# starduino.net
KiCad netlist of a schematic drawn in EAGLE
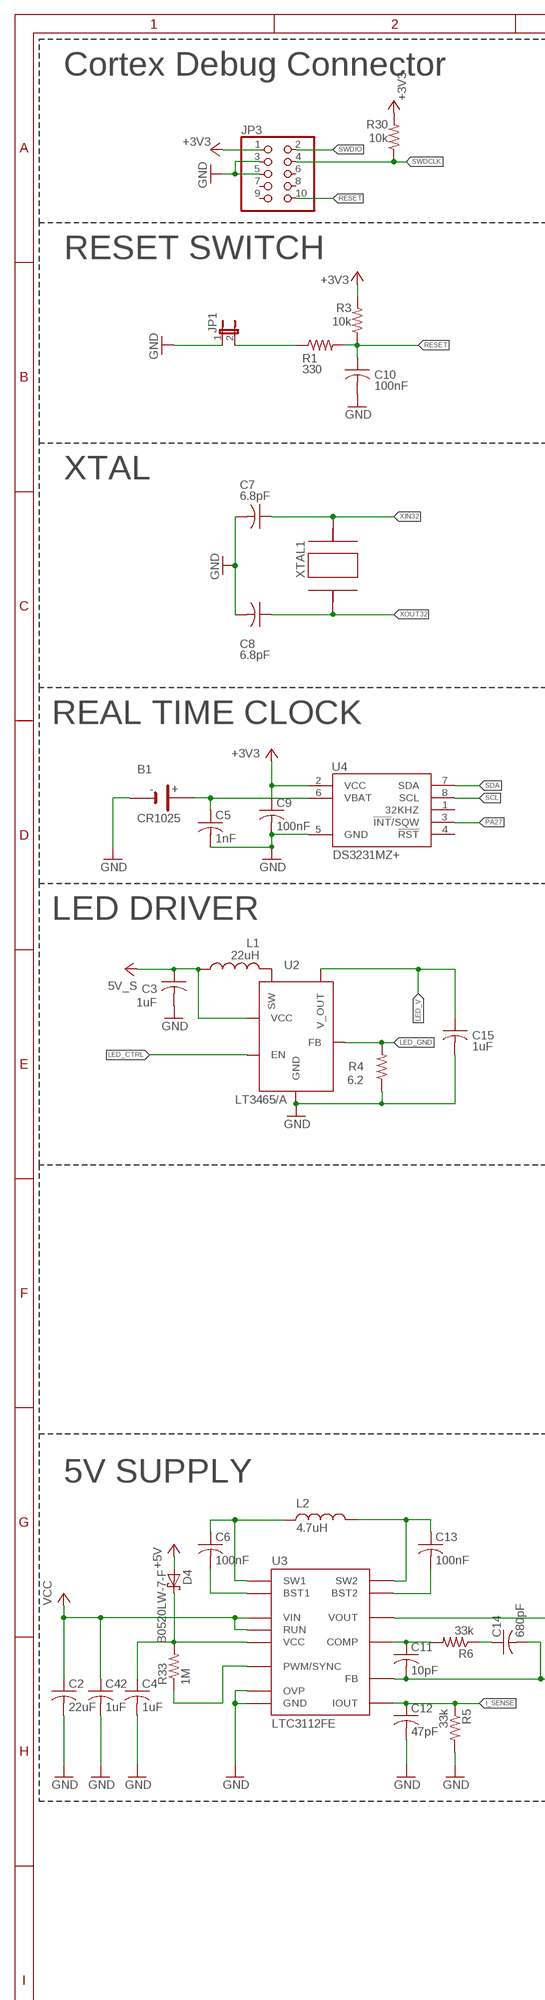
[diagram p0: schematic, sheet 1, part 1 of 2]
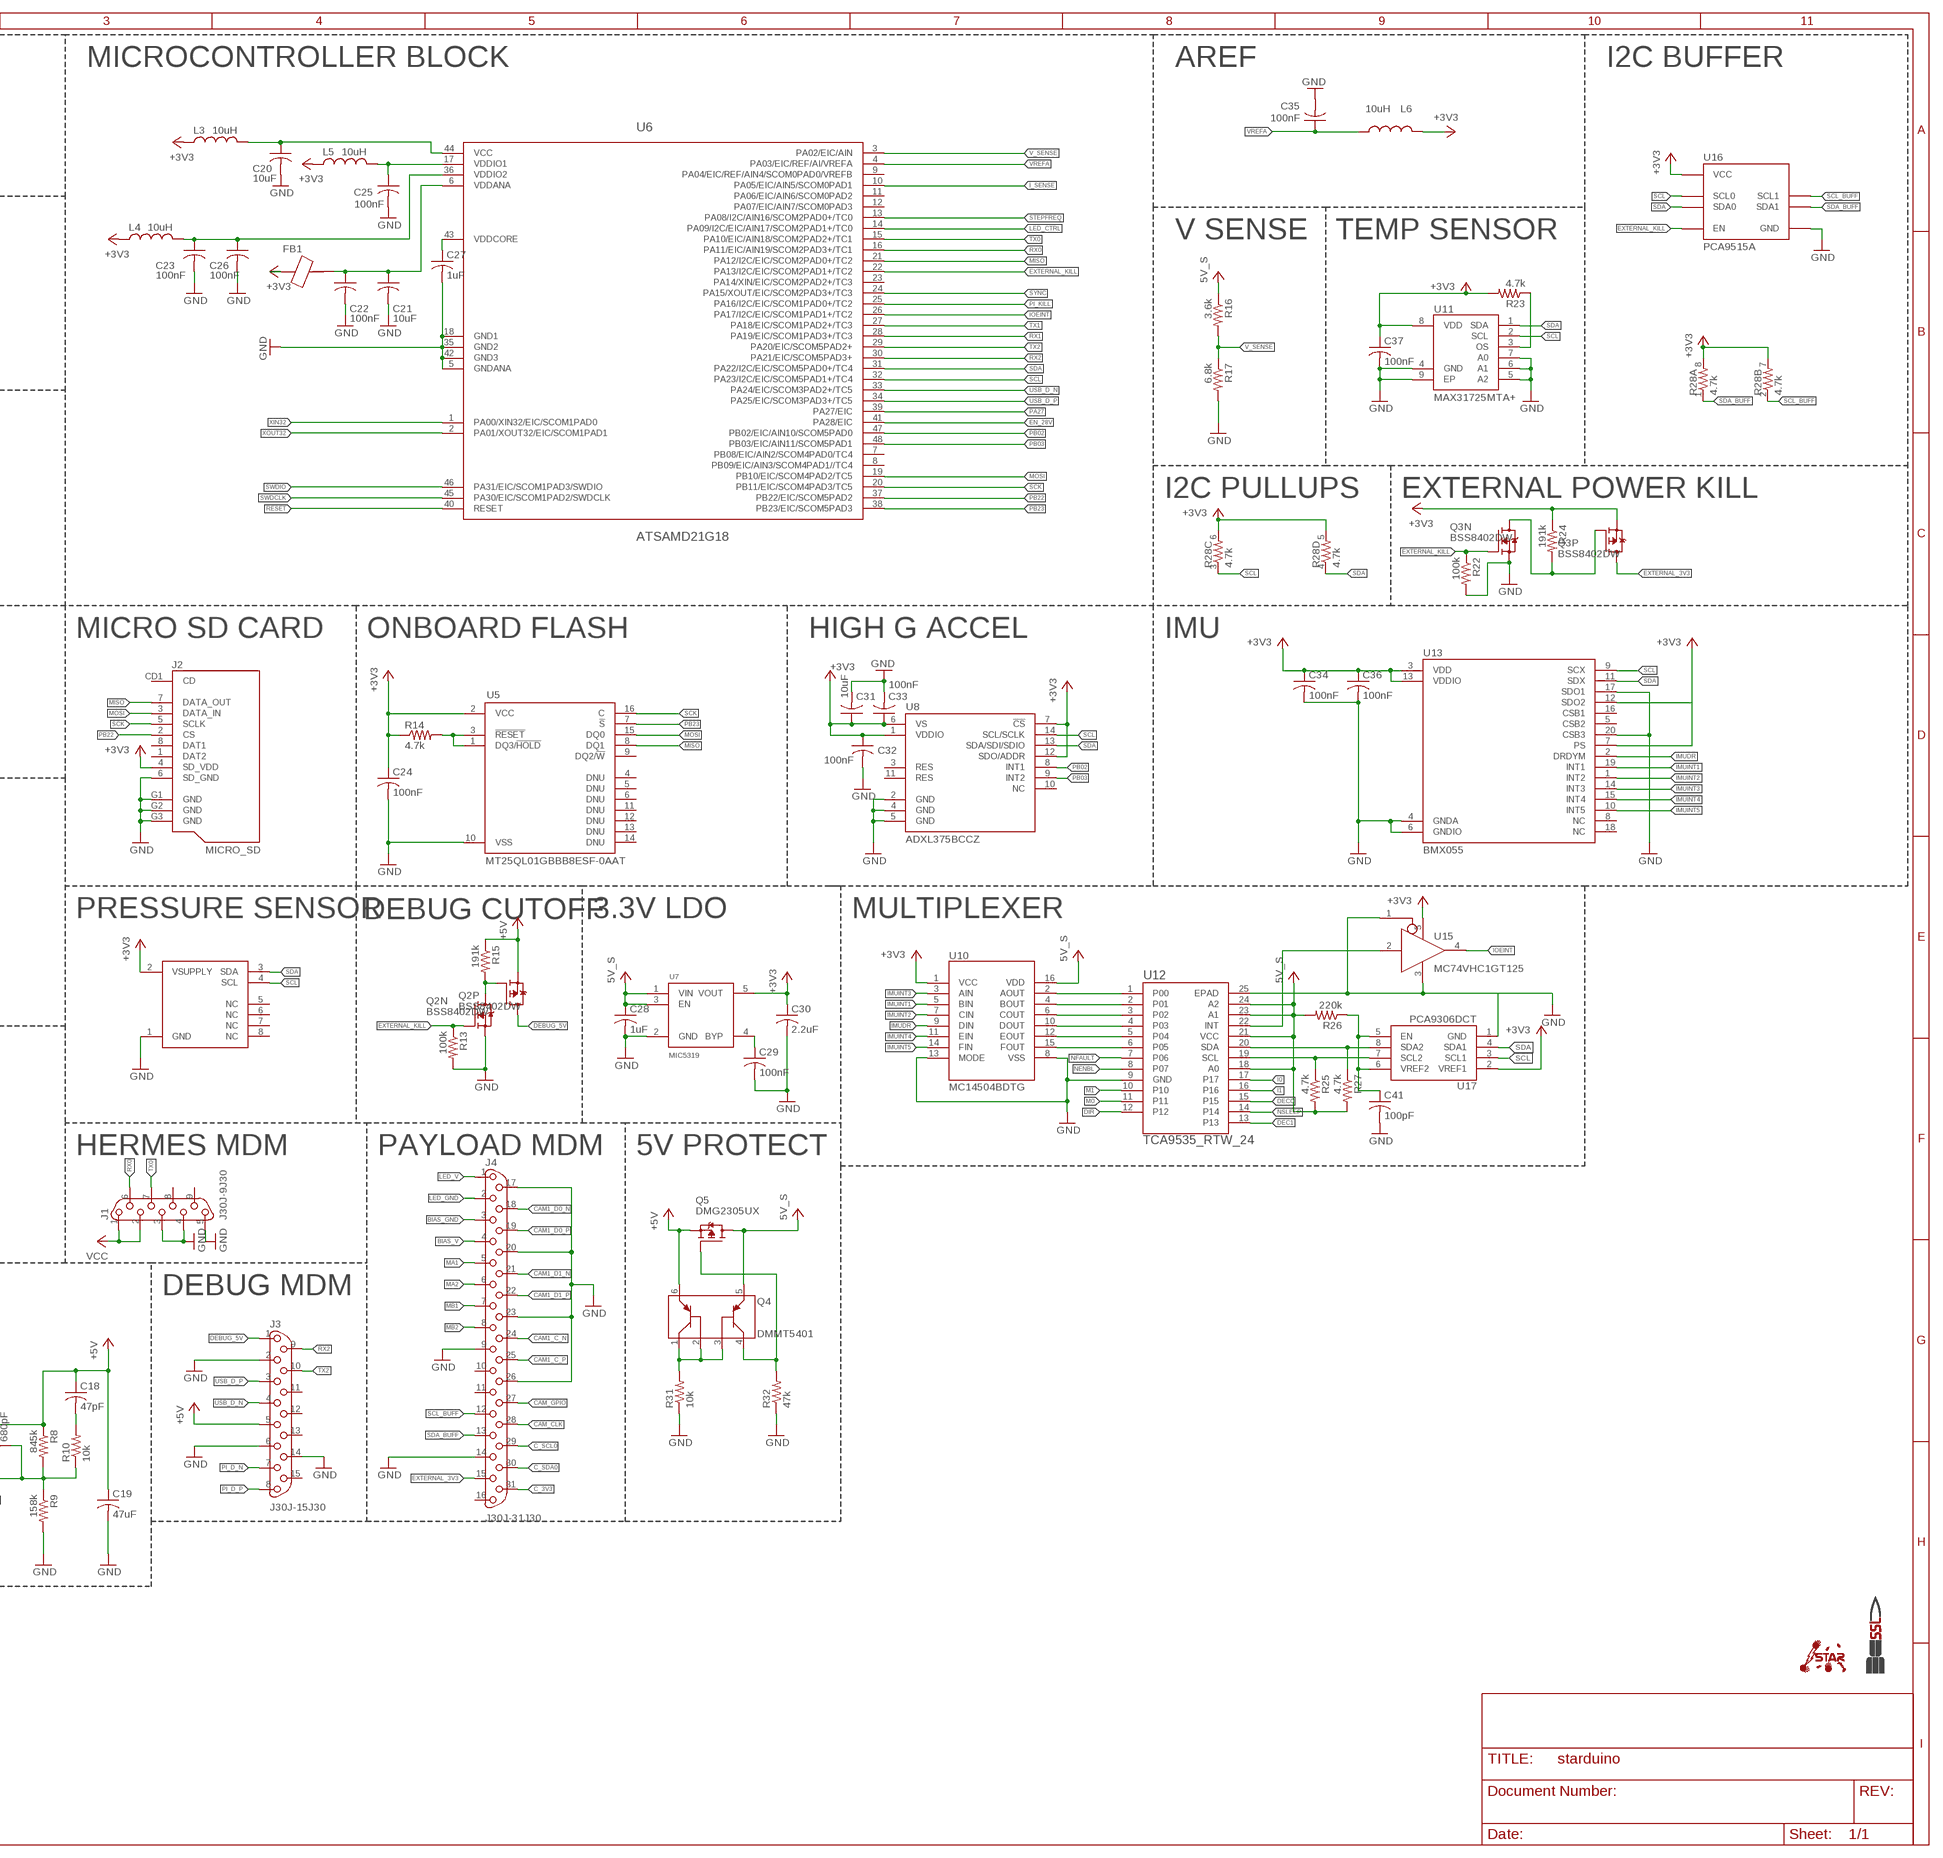
[diagram p1: schematic, sheet 1, part 2 of 2]

(export (version "E")
  (design (tool "Eeschema 10.0.6"))
  (components
    (comp (ref "B1")
      (value "CR1025")
      (footprint "eagle-import:CR1025")
      (libsource (lib "eagle-import") (part "CR1025"))
    )
    (comp (ref "C2")
      (value "22uF")
      (footprint "eagle-import:C1206")
      (libsource (lib "eagle-import") (part "resistor_C-USC1206"))
    )
    (comp (ref "C3")
      (value "1uF")
      (footprint "eagle-import:C0603")
      (libsource (lib "eagle-import") (part "resistor_C-USC0603"))
    )
    (comp (ref "C4")
      (value "1uF")
      (footprint "eagle-import:C0603")
      (libsource (lib "eagle-import") (part "resistor_C-USC0603"))
    )
    (comp (ref "C5")
      (value "1nF")
      (footprint "eagle-import:C0603")
      (libsource (lib "eagle-import") (part "resistor_C-USC0603"))
    )
    (comp (ref "C6")
      (value "100nF")
      (footprint "eagle-import:C0603")
      (libsource (lib "eagle-import") (part "resistor_C-USC0603"))
    )
    (comp (ref "C7")
      (value "6.8pF")
      (footprint "eagle-import:C0603")
      (libsource (lib "eagle-import") (part "resistor_C-USC0603"))
    )
    (comp (ref "C8")
      (value "6.8pF")
      (footprint "eagle-import:C0603")
      (libsource (lib "eagle-import") (part "resistor_C-USC0603"))
    )
    (comp (ref "C9")
      (value "100nF")
      (footprint "eagle-import:C0603")
      (libsource (lib "eagle-import") (part "resistor_C-USC0603"))
    )
    (comp (ref "C10")
      (value "100nF")
      (footprint "eagle-import:C0603")
      (libsource (lib "eagle-import") (part "resistor_C-USC0603"))
    )
    (comp (ref "C11")
      (value "10pF")
      (footprint "eagle-import:C0603")
      (libsource (lib "eagle-import") (part "resistor_C-USC0603"))
    )
    (comp (ref "C12")
      (value "47pF")
      (footprint "eagle-import:C0603")
      (libsource (lib "eagle-import") (part "resistor_C-USC0603"))
    )
    (comp (ref "C13")
      (value "100nF")
      (footprint "eagle-import:C0603")
      (libsource (lib "eagle-import") (part "resistor_C-USC0603"))
    )
    (comp (ref "C14")
      (value "680pF")
      (footprint "eagle-import:C0603")
      (libsource (lib "eagle-import") (part "resistor_C-USC0603"))
    )
    (comp (ref "C15")
      (value "1uF")
      (footprint "eagle-import:C0603")
      (libsource (lib "eagle-import") (part "resistor_C-USC0603"))
    )
    (comp (ref "C18")
      (value "47pF")
      (footprint "eagle-import:C0603")
      (libsource (lib "eagle-import") (part "resistor_C-USC0603"))
    )
    (comp (ref "C19")
      (value "47uF")
      (footprint "eagle-import:C1210")
      (libsource (lib "eagle-import") (part "resistor_C-USC1210"))
    )
    (comp (ref "C20")
      (value "10uF")
      (footprint "eagle-import:C0603")
      (libsource (lib "eagle-import") (part "resistor_C-USC0603"))
    )
    (comp (ref "C21")
      (value "10uF")
      (footprint "eagle-import:C0603")
      (libsource (lib "eagle-import") (part "resistor_C-USC0603"))
    )
    (comp (ref "C22")
      (value "100nF")
      (footprint "eagle-import:C0603")
      (libsource (lib "eagle-import") (part "resistor_C-USC0603"))
    )
    (comp (ref "C23")
      (value "100nF")
      (footprint "eagle-import:C0603")
      (libsource (lib "eagle-import") (part "resistor_C-USC0603"))
    )
    (comp (ref "C24")
      (value "100nF")
      (footprint "eagle-import:C0603")
      (libsource (lib "eagle-import") (part "resistor_C-USC0603"))
    )
    (comp (ref "C25")
      (value "100nF")
      (footprint "eagle-import:C0603")
      (libsource (lib "eagle-import") (part "resistor_C-USC0603"))
    )
    (comp (ref "C26")
      (value "100nF")
      (footprint "eagle-import:C0603")
      (libsource (lib "eagle-import") (part "resistor_C-USC0603"))
    )
    (comp (ref "C27")
      (value "1uF")
      (footprint "eagle-import:C0603")
      (libsource (lib "eagle-import") (part "resistor_C-USC0603"))
    )
    (comp (ref "C28")
      (value "1uF")
      (footprint "eagle-import:C0603")
      (libsource (lib "eagle-import") (part "resistor_C-USC0603"))
    )
    (comp (ref "C29")
      (value "100nF")
      (footprint "eagle-import:C0603")
      (libsource (lib "eagle-import") (part "resistor_C-USC0603"))
    )
    (comp (ref "C30")
      (value "2.2uF")
      (footprint "eagle-import:C0603")
      (libsource (lib "eagle-import") (part "resistor_C-USC0603"))
    )
    (comp (ref "C31")
      (value "10uF")
      (footprint "eagle-import:C0603")
      (libsource (lib "eagle-import") (part "resistor_C-USC0603"))
    )
    (comp (ref "C32")
      (value "100nF")
      (footprint "eagle-import:C0603")
      (libsource (lib "eagle-import") (part "resistor_C-USC0603"))
    )
    (comp (ref "C33")
      (value "100nF")
      (footprint "eagle-import:C0603")
      (libsource (lib "eagle-import") (part "resistor_C-USC0603"))
    )
    (comp (ref "C34")
      (value "100nF")
      (footprint "eagle-import:C0603")
      (libsource (lib "eagle-import") (part "resistor_C-USC0603"))
    )
    (comp (ref "C35")
      (value "100nF")
      (footprint "eagle-import:C0603")
      (libsource (lib "eagle-import") (part "resistor_C-USC0603"))
    )
    (comp (ref "C36")
      (value "100nF")
      (footprint "eagle-import:C0603")
      (libsource (lib "eagle-import") (part "resistor_C-USC0603"))
    )
    (comp (ref "C37")
      (value "100nF")
      (footprint "eagle-import:C0603")
      (libsource (lib "eagle-import") (part "resistor_C-USC0603"))
    )
    (comp (ref "C41")
      (value "100pF")
      (footprint "eagle-import:C0603")
      (libsource (lib "eagle-import") (part "C-USC0603"))
    )
    (comp (ref "C42")
      (value "1uF")
      (footprint "eagle-import:C0603")
      (libsource (lib "eagle-import") (part "resistor_C-USC0603"))
    )
    (comp (ref "D4")
      (value "B0520LW-7-F")
      (footprint "eagle-import:SOD123")
      (libsource (lib "eagle-import") (part "SCHOTTKY-DIODESOD123"))
    )
    (comp (ref "FB1")
      (value "BLM18KG221BH1D")
      (footprint "eagle-import:0603")
      (libsource (lib "eagle-import") (part "FERRITE_BEAD-0603"))
    )
    (comp (ref "J1")
      (value "J30J-9J30")
      (footprint "eagle-import:ZKN-9-J30")
      (libsource (lib "eagle-import") (part "J30J-9J30"))
    )
    (comp (ref "J2")
      (value "MICRO_SD")
      (footprint "eagle-import:MICROSD_PUSH_PUSH_AMPHENOL")
      (libsource (lib "eagle-import") (part "MICRO_SD"))
    )
    (comp (ref "J3")
      (value "J30J-15J30")
      (footprint "eagle-import:ZKN-15-J30")
      (libsource (lib "eagle-import") (part "J30J-15J30"))
    )
    (comp (ref "J4")
      (value "J30J-31J30")
      (footprint "eagle-import:ZKN-31-J30")
      (libsource (lib "eagle-import") (part "J30J-31J30"))
    )
    (comp (ref "JP1")
      (value "JUMPER-2PTH")
      (footprint "eagle-import:1X02")
      (libsource (lib "eagle-import") (part "JUMPER-2PTH"))
    )
    (comp (ref "JP3")
      (value "PINHD-2X5")
      (footprint "eagle-import:2X05")
      (libsource (lib "eagle-import") (part "PINHD-2X5"))
    )
    (comp (ref "L1")
      (value "22uH")
      (footprint "eagle-import:VLF504012MT(TDK)")
      (libsource (lib "eagle-import") (part "INDUCTOR-VLF504012MT"))
    )
    (comp (ref "L2")
      (value "4.7uH")
      (footprint "eagle-import:SRP5030")
      (libsource (lib "eagle-import") (part "SRP5030T"))
    )
    (comp (ref "L3")
      (value "10uH")
      (footprint "eagle-import:0603")
      (libsource (lib "eagle-import") (part "INDUCTOR-0603"))
    )
    (comp (ref "L4")
      (value "10uH")
      (footprint "eagle-import:0603")
      (libsource (lib "eagle-import") (part "INDUCTOR-0603"))
    )
    (comp (ref "L5")
      (value "10uH")
      (footprint "eagle-import:0603")
      (libsource (lib "eagle-import") (part "INDUCTOR-0603"))
    )
    (comp (ref "L6")
      (value "10uH")
      (footprint "eagle-import:0603")
      (libsource (lib "eagle-import") (part "INDUCTOR-0603"))
    )
    (comp (ref "Q2")
      (value "BSS8402DW")
      (footprint "eagle-import:SC70")
      (libsource (lib "eagle-import") (part "BSS8402DW"))
    )
    (comp (ref "Q3")
      (value "BSS8402DW")
      (footprint "eagle-import:SC70")
      (libsource (lib "eagle-import") (part "BSS8402DW"))
    )
    (comp (ref "Q4")
      (value "DMMT5401")
      (footprint "eagle-import:SOT-26")
      (libsource (lib "eagle-import") (part "DMMT5401"))
    )
    (comp (ref "Q5")
      (value "DMG2305UX")
      (footprint "eagle-import:SOT23")
      (libsource (lib "eagle-import") (part "DMG2305UX"))
    )
    (comp (ref "R1")
      (value "330")
      (footprint "eagle-import:R0603")
      (libsource (lib "eagle-import") (part "resistor_R-US_R0603"))
    )
    (comp (ref "R3")
      (value "10k")
      (footprint "eagle-import:R0603")
      (libsource (lib "eagle-import") (part "resistor_R-US_R0603"))
    )
    (comp (ref "R4")
      (value "6.2")
      (footprint "eagle-import:R0603")
      (libsource (lib "eagle-import") (part "resistor_R-US_R0603"))
    )
    (comp (ref "R5")
      (value "33k")
      (footprint "eagle-import:R0603")
      (libsource (lib "eagle-import") (part "resistor_R-US_R0603"))
    )
    (comp (ref "R6")
      (value "33k")
      (footprint "eagle-import:R0603")
      (libsource (lib "eagle-import") (part "resistor_R-US_R0603"))
    )
    (comp (ref "R8")
      (value "845k")
      (footprint "eagle-import:R0603")
      (libsource (lib "eagle-import") (part "resistor_R-US_R0603"))
    )
    (comp (ref "R9")
      (value "158k")
      (footprint "eagle-import:R0603")
      (libsource (lib "eagle-import") (part "resistor_R-US_R0603"))
    )
    (comp (ref "R10")
      (value "10k")
      (footprint "eagle-import:R0603")
      (libsource (lib "eagle-import") (part "resistor_R-US_R0603"))
    )
    (comp (ref "R13")
      (value "100k")
      (footprint "eagle-import:R0603")
      (libsource (lib "eagle-import") (part "resistor_R-US_R0603"))
    )
    (comp (ref "R14")
      (value "4.7k")
      (footprint "eagle-import:R0603")
      (libsource (lib "eagle-import") (part "resistor_R-US_R0603"))
    )
    (comp (ref "R15")
      (value "191k")
      (footprint "eagle-import:R0603")
      (libsource (lib "eagle-import") (part "resistor_R-US_R0603"))
    )
    (comp (ref "R16")
      (value "3.6k")
      (footprint "eagle-import:R0603")
      (libsource (lib "eagle-import") (part "resistor_R-US_R0603"))
    )
    (comp (ref "R17")
      (value "6.8k")
      (footprint "eagle-import:R0603")
      (libsource (lib "eagle-import") (part "resistor_R-US_R0603"))
    )
    (comp (ref "R22")
      (value "100k")
      (footprint "eagle-import:R0603")
      (libsource (lib "eagle-import") (part "resistor_R-US_R0603"))
    )
    (comp (ref "R23")
      (value "4.7k")
      (footprint "eagle-import:R0603")
      (libsource (lib "eagle-import") (part "resistor_R-US_R0603"))
    )
    (comp (ref "R24")
      (value "191k")
      (footprint "eagle-import:R0603")
      (libsource (lib "eagle-import") (part "resistor_R-US_R0603"))
    )
    (comp (ref "R25")
      (value "4.7k")
      (footprint "eagle-import:R0603")
      (libsource (lib "eagle-import") (part "R-US_R0603"))
    )
    (comp (ref "R26")
      (value "220k")
      (footprint "eagle-import:R0603")
      (libsource (lib "eagle-import") (part "R-US_R0603"))
    )
    (comp (ref "R27")
      (value "4.7k")
      (footprint "eagle-import:R0603")
      (libsource (lib "eagle-import") (part "R-US_R0603"))
    )
    (comp (ref "R28")
      (value "4.7k")
      (footprint "eagle-import:0603-ARV")
      (libsource (lib "eagle-import") (part "RESISTOR-ARRAY0603-ARV"))
    )
    (comp (ref "R30")
      (value "10k")
      (footprint "eagle-import:R0603")
      (libsource (lib "eagle-import") (part "resistor_R-US_R0603"))
    )
    (comp (ref "R31")
      (value "10k")
      (footprint "eagle-import:R0603")
      (libsource (lib "eagle-import") (part "resistor_R-US_R0603"))
    )
    (comp (ref "R32")
      (value "47k")
      (footprint "eagle-import:R0603")
      (libsource (lib "eagle-import") (part "resistor_R-US_R0603"))
    )
    (comp (ref "R33")
      (value "1M")
      (footprint "eagle-import:R0603")
      (libsource (lib "eagle-import") (part "resistor_R-US_R0603"))
    )
    (comp (ref "U$1")
      (value "STAR")
      (footprint "eagle-import:STAR_.3IN")
      (libsource (lib "eagle-import") (part "STAR"))
    )
    (comp (ref "U$2")
      (value "SSL.3IN_SILK")
      (footprint "eagle-import:SSL_SILK_.3IN")
      (libsource (lib "eagle-import") (part "SSL.3IN_SILK"))
    )
    (comp (ref "U1")
      (value "SSCMNNN015PA2A3")
      (footprint "eagle-import:HSC-SMT-8")
      (libsource (lib "eagle-import") (part "SSCMNNN015PA2A3"))
    )
    (comp (ref "U2")
      (value "LT3465/A")
      (footprint "eagle-import:SOT23-6")
      (libsource (lib "eagle-import") (part "LT3465/A"))
    )
    (comp (ref "U3")
      (value "LTC3112FE")
      (footprint "eagle-import:TSSOP20")
      (libsource (lib "eagle-import") (part "LTC3112FE"))
    )
    (comp (ref "U4")
      (value "DS3231MZ+")
      (footprint "eagle-import:SOIC-8")
      (libsource (lib "eagle-import") (part "DS3231MZ+"))
    )
    (comp (ref "U5")
      (value "MT25QL01GBBB8ESF-0AAT")
      (footprint "eagle-import:SOP2-16")
      (libsource (lib "eagle-import") (part "MT25QL01GBBB8ESF-0AAT"))
    )
    (comp (ref "U6")
      (value "ATSAMD21G18")
      (footprint "eagle-import:48-TQFP")
      (libsource (lib "eagle-import") (part "ATSAMD21G18"))
    )
    (comp (ref "U7")
      (value "MIC5319")
      (footprint "eagle-import:SOT23-5L")
      (libsource (lib "eagle-import") (part "MIC5319"))
    )
    (comp (ref "U8")
      (value "ADXL375BCCZ")
      (footprint "eagle-import:LGA-14")
      (libsource (lib "eagle-import") (part "ADXL375BCCZ"))
    )
    (comp (ref "U10")
      (value "MC14504BDTG")
      (footprint "eagle-import:TSSOP16")
      (libsource (lib "eagle-import") (part "MC14504BDTG"))
    )
    (comp (ref "U11")
      (value "MAX31725MTA+")
      (footprint "eagle-import:DFN-8")
      (libsource (lib "eagle-import") (part "MAX31725MTA+"))
    )
    (comp (ref "U12")
      (value "TCA9535_RTW_24")
      (footprint "eagle-import:RTW24_2P45X2P45")
      (fields (field (name "MANUFACTURER_PART_NUMBER") "tca9535_rtw_24"))
      (libsource (lib "eagle-import") (part "TCA9535_RTW_24"))
    )
    (comp (ref "U13")
      (value "BMX055")
      (footprint "eagle-import:LGA-20")
      (libsource (lib "eagle-import") (part "BMX055"))
    )
    (comp (ref "U15")
      (value "MC74VHC1GT125")
      (footprint "eagle-import:SC-70-5")
      (libsource (lib "eagle-import") (part "MC74VHC1GT125"))
    )
    (comp (ref "U16")
      (value "PCA9515A")
      (footprint "eagle-import:TSSOP8")
      (libsource (lib "eagle-import") (part "PCA9515A"))
    )
    (comp (ref "U17")
      (value "PCA9306DCT")
      (footprint "eagle-import:SSOP8")
      (libsource (lib "eagle-import") (part "PCA9306DCT"))
    )
    (comp (ref "XTAL1")
      (value "ABS07AIG-32.768KHZ-1-T")
      (footprint "eagle-import:2-SMD")
      (libsource (lib "eagle-import") (part "ABS07AIG-32.768KHZ-1-T"))
    )
  )
  (nets
    (net (code "1") (name "+3V3") (class "Default")
      (node (ref "C24") (pin "1") (pinfunction "1_1") (pintype "passive"))
      (node (ref "C30") (pin "1") (pinfunction "1_1") (pintype "passive"))
      (node (ref "C31") (pin "1") (pinfunction "1_1") (pintype "passive"))
      (node (ref "C32") (pin "1") (pinfunction "1_1") (pintype "passive"))
      (node (ref "C33") (pin "1") (pinfunction "1_1") (pintype "passive"))
      (node (ref "C34") (pin "1") (pinfunction "1_1") (pintype "passive"))
      (node (ref "C36") (pin "1") (pinfunction "1_1") (pintype "passive"))
      (node (ref "C37") (pin "1") (pinfunction "1_1") (pintype "passive"))
      (node (ref "C9") (pin "1") (pinfunction "1_1") (pintype "passive"))
      (node (ref "FB1") (pin "1") (pinfunction "P$1_1") (pintype "passive"))
      (node (ref "J2") (pin "4") (pinfunction "SD_VDD_4") (pintype "power_in"))
      (node (ref "JP3") (pin "1") (pinfunction "1_1") (pintype "passive"))
      (node (ref "L3") (pin "1") (pinfunction "1_1") (pintype "passive"))
      (node (ref "L4") (pin "1") (pinfunction "1_1") (pintype "passive"))
      (node (ref "L5") (pin "1") (pinfunction "1_1") (pintype "passive"))
      (node (ref "L6") (pin "2") (pinfunction "2_2") (pintype "passive"))
      (node (ref "Q3") (pin "4") (pinfunction "S_4") (pintype "passive"))
      (node (ref "R14") (pin "1") (pinfunction "1_1") (pintype "passive"))
      (node (ref "R23") (pin "2") (pinfunction "2_2") (pintype "passive"))
      (node (ref "R24") (pin "1") (pinfunction "1_1") (pintype "passive"))
      (node (ref "R28") (pin "5") (pinfunction "2_5") (pintype "passive"))
      (node (ref "R28") (pin "6") (pinfunction "2_6") (pintype "passive"))
      (node (ref "R28") (pin "7") (pinfunction "2_7") (pintype "passive"))
      (node (ref "R28") (pin "8") (pinfunction "2_8") (pintype "passive"))
      (node (ref "R3") (pin "2") (pinfunction "2_2") (pintype "passive"))
      (node (ref "R30") (pin "2") (pinfunction "2_2") (pintype "passive"))
      (node (ref "U1") (pin "2") (pinfunction "VSUPPLY_2") (pintype "power_in"))
      (node (ref "U10") (pin "1") (pinfunction "VCC_1") (pintype "power_in"))
      (node (ref "U11") (pin "8") (pinfunction "VDD_8") (pintype "power_in"))
      (node (ref "U13") (pin "12") (pinfunction "SDO2_12") (pintype "bidirectional"))
      (node (ref "U13") (pin "13") (pinfunction "VDDIO_13") (pintype "power_in"))
      (node (ref "U13") (pin "3") (pinfunction "VDD_3") (pintype "power_in"))
      (node (ref "U13") (pin "7") (pinfunction "PS_7") (pintype "bidirectional"))
      (node (ref "U15") (pin "5") (pinfunction "VIN_5") (pintype "bidirectional"))
      (node (ref "U16") (pin "P$8") (pinfunction "VCC_P$8") (pintype "bidirectional"))
      (node (ref "U17") (pin "2") (pinfunction "VREF1_2") (pintype "power_in"))
      (node (ref "U4") (pin "2") (pinfunction "VCC_2") (pintype "power_in"))
      (node (ref "U5") (pin "2") (pinfunction "VCC_2") (pintype "bidirectional"))
      (node (ref "U7") (pin "5") (pinfunction "VOUT_5") (pintype "bidirectional"))
      (node (ref "U8") (pin "1") (pinfunction "VDDIO_1") (pintype "bidirectional"))
      (node (ref "U8") (pin "12") (pinfunction "SDO/ADDR_12") (pintype "bidirectional"))
      (node (ref "U8") (pin "6") (pinfunction "VS_6") (pintype "bidirectional"))
      (node (ref "U8") (pin "7") (pinfunction "~{CS}_7") (pintype "bidirectional"))
    )
    (net (code "2") (name "+5V") (class "Default")
      (node (ref "C18") (pin "1") (pinfunction "1_1") (pintype "passive"))
      (node (ref "C19") (pin "1") (pinfunction "1_1") (pintype "passive"))
      (node (ref "D4") (pin "A") (pinfunction "A_A") (pintype "passive"))
      (node (ref "J3") (pin "5") (pinfunction "5_5") (pintype "bidirectional"))
      (node (ref "Q2") (pin "4") (pinfunction "S_4") (pintype "passive"))
      (node (ref "Q4") (pin "6") (pinfunction "E1_6") (pintype "bidirectional"))
      (node (ref "Q5") (pin "2") (pinfunction "S_2") (pintype "passive"))
      (node (ref "R15") (pin "1") (pinfunction "1_1") (pintype "passive"))
      (node (ref "R8") (pin "1") (pinfunction "1_1") (pintype "passive"))
      (node (ref "U3") (pin "9") (pinfunction "VOUT_9") (pintype "bidirectional"))
    )
    (net (code "3") (name "5V_S") (class "Default")
      (node (ref "C28") (pin "1") (pinfunction "1_1") (pintype "passive"))
      (node (ref "C3") (pin "1") (pinfunction "1_1") (pintype "passive"))
      (node (ref "L1") (pin "P$1") (pinfunction "1_P$1") (pintype "passive"))
      (node (ref "Q4") (pin "5") (pinfunction "E2_5") (pintype "bidirectional"))
      (node (ref "Q5") (pin "3") (pinfunction "D_3") (pintype "passive"))
      (node (ref "R16") (pin "1") (pinfunction "1_1") (pintype "passive"))
      (node (ref "R25") (pin "2") (pinfunction "2_2") (pintype "passive"))
      (node (ref "R26") (pin "2") (pinfunction "2_2") (pintype "passive"))
      (node (ref "R27") (pin "2") (pinfunction "2_2") (pintype "passive"))
      (node (ref "U10") (pin "16") (pinfunction "VDD_16") (pintype "power_in"))
      (node (ref "U12") (pin "18") (pinfunction "A0_18") (pintype "input"))
      (node (ref "U12") (pin "21") (pinfunction "VCC_21") (pintype "power_in"))
      (node (ref "U12") (pin "23") (pinfunction "A1_23") (pintype "input"))
      (node (ref "U12") (pin "24") (pinfunction "A2_24") (pintype "input"))
      (node (ref "U2") (pin "5") (pinfunction "VCC_5") (pintype "bidirectional"))
      (node (ref "U7") (pin "1") (pinfunction "VIN_1") (pintype "bidirectional"))
      (node (ref "U7") (pin "3") (pinfunction "EN_3") (pintype "bidirectional"))
    )
    (net (code "4") (name "BIAS_GND") (class "Default")
      (node (ref "J4") (pin "3") (pinfunction "3_3") (pintype "bidirectional"))
    )
    (net (code "5") (name "BIAS_V") (class "Default")
      (node (ref "J4") (pin "4") (pinfunction "4_4") (pintype "bidirectional"))
    )
    (net (code "6") (name "CAM1_C_N") (class "Default")
      (node (ref "J4") (pin "24") (pinfunction "24_24") (pintype "bidirectional"))
    )
    (net (code "7") (name "CAM1_C_P") (class "Default")
      (node (ref "J4") (pin "25") (pinfunction "25_25") (pintype "bidirectional"))
    )
    (net (code "8") (name "CAM1_D0_N") (class "Default")
      (node (ref "J4") (pin "18") (pinfunction "18_18") (pintype "bidirectional"))
    )
    (net (code "9") (name "CAM1_D0_P") (class "Default")
      (node (ref "J4") (pin "19") (pinfunction "19_19") (pintype "bidirectional"))
    )
    (net (code "10") (name "CAM1_D1_N") (class "Default")
      (node (ref "J4") (pin "21") (pinfunction "21_21") (pintype "bidirectional"))
    )
    (net (code "11") (name "CAM1_D1_P") (class "Default")
      (node (ref "J4") (pin "22") (pinfunction "22_22") (pintype "bidirectional"))
    )
    (net (code "12") (name "CAM_CLK") (class "Default")
      (node (ref "J4") (pin "28") (pinfunction "28_28") (pintype "bidirectional"))
    )
    (net (code "13") (name "CAM_GPIO") (class "Default")
      (node (ref "J4") (pin "27") (pinfunction "27_27") (pintype "bidirectional"))
    )
    (net (code "14") (name "C_3V3") (class "Default")
      (node (ref "J4") (pin "31") (pinfunction "31_31") (pintype "bidirectional"))
    )
    (net (code "15") (name "C_SCL0") (class "Default")
      (node (ref "J4") (pin "29") (pinfunction "29_29") (pintype "bidirectional"))
    )
    (net (code "16") (name "C_SDA0") (class "Default")
      (node (ref "J4") (pin "30") (pinfunction "30_30") (pintype "bidirectional"))
    )
    (net (code "17") (name "DEBUG_5V") (class "Default")
      (node (ref "J3") (pin "1") (pinfunction "1_1") (pintype "bidirectional"))
      (node (ref "Q2") (pin "3") (pinfunction "D_3") (pintype "passive"))
    )
    (net (code "18") (name "DEC0") (class "Default")
      (node (ref "U12") (pin "15") (pinfunction "P15_15") (pintype "bidirectional"))
    )
    (net (code "19") (name "DEC1") (class "Default")
      (node (ref "U12") (pin "13") (pinfunction "P13_13") (pintype "bidirectional"))
    )
    (net (code "20") (name "DIR") (class "Default")
      (node (ref "U12") (pin "12") (pinfunction "P12_12") (pintype "bidirectional"))
    )
    (net (code "21") (name "EN_28V") (class "Default")
      (node (ref "U6") (pin "41") (pinfunction "PA28/EIC_41") (pintype "bidirectional"))
    )
    (net (code "22") (name "EXTERNAL_3V3") (class "Default")
      (node (ref "J4") (pin "15") (pinfunction "15_15") (pintype "bidirectional"))
      (node (ref "Q3") (pin "3") (pinfunction "D_3") (pintype "passive"))
    )
    (net (code "23") (name "EXTERNAL_KILL") (class "Default")
      (node (ref "Q2") (pin "2") (pinfunction "G_2") (pintype "passive"))
      (node (ref "Q3") (pin "2") (pinfunction "G_2") (pintype "passive"))
      (node (ref "R13") (pin "1") (pinfunction "1_1") (pintype "passive"))
      (node (ref "R22") (pin "1") (pinfunction "1_1") (pintype "passive"))
      (node (ref "U16") (pin "P$5") (pinfunction "EN_P$5") (pintype "bidirectional"))
      (node (ref "U6") (pin "22") (pinfunction "PA13/I2C/EIC/SCOM2PAD1+/TC2_22") (pintype "bidirectional"))
    )
    (net (code "24") (name "GND") (class "Default")
      (node (ref "B1") (pin "3") (pinfunction "-_3") (pintype "power_in"))
      (node (ref "C10") (pin "2") (pinfunction "2_2") (pintype "passive"))
      (node (ref "C12") (pin "2") (pinfunction "2_2") (pintype "passive"))
      (node (ref "C15") (pin "2") (pinfunction "2_2") (pintype "passive"))
      (node (ref "C19") (pin "2") (pinfunction "2_2") (pintype "passive"))
      (node (ref "C2") (pin "2") (pinfunction "2_2") (pintype "passive"))
      (node (ref "C20") (pin "2") (pinfunction "2_2") (pintype "passive"))
      (node (ref "C21") (pin "2") (pinfunction "2_2") (pintype "passive"))
      (node (ref "C22") (pin "2") (pinfunction "2_2") (pintype "passive"))
      (node (ref "C23") (pin "2") (pinfunction "2_2") (pintype "passive"))
      (node (ref "C24") (pin "2") (pinfunction "2_2") (pintype "passive"))
      (node (ref "C25") (pin "2") (pinfunction "2_2") (pintype "passive"))
      (node (ref "C26") (pin "2") (pinfunction "2_2") (pintype "passive"))
      (node (ref "C27") (pin "2") (pinfunction "2_2") (pintype "passive"))
      (node (ref "C28") (pin "2") (pinfunction "2_2") (pintype "passive"))
      (node (ref "C29") (pin "2") (pinfunction "2_2") (pintype "passive"))
      (node (ref "C3") (pin "2") (pinfunction "2_2") (pintype "passive"))
      (node (ref "C30") (pin "2") (pinfunction "2_2") (pintype "passive"))
      (node (ref "C31") (pin "2") (pinfunction "2_2") (pintype "passive"))
      (node (ref "C32") (pin "2") (pinfunction "2_2") (pintype "passive"))
      (node (ref "C33") (pin "2") (pinfunction "2_2") (pintype "passive"))
      (node (ref "C34") (pin "2") (pinfunction "2_2") (pintype "passive"))
      (node (ref "C35") (pin "2") (pinfunction "2_2") (pintype "passive"))
      (node (ref "C36") (pin "2") (pinfunction "2_2") (pintype "passive"))
      (node (ref "C37") (pin "2") (pinfunction "2_2") (pintype "passive"))
      (node (ref "C4") (pin "2") (pinfunction "2_2") (pintype "passive"))
      (node (ref "C41") (pin "2") (pinfunction "2_2") (pintype "passive"))
      (node (ref "C42") (pin "2") (pinfunction "2_2") (pintype "passive"))
      (node (ref "C5") (pin "2") (pinfunction "2_2") (pintype "passive"))
      (node (ref "C7") (pin "2") (pinfunction "2_2") (pintype "passive"))
      (node (ref "C8") (pin "2") (pinfunction "2_2") (pintype "passive"))
      (node (ref "C9") (pin "2") (pinfunction "2_2") (pintype "passive"))
      (node (ref "J1") (pin "3") (pinfunction "3_3") (pintype "bidirectional"))
      (node (ref "J1") (pin "4") (pinfunction "4_4") (pintype "bidirectional"))
      (node (ref "J1") (pin "5") (pinfunction "5_5") (pintype "bidirectional"))
      (node (ref "J2") (pin "6") (pinfunction "SD_GND_6") (pintype "power_in"))
      (node (ref "J2") (pin "G1") (pinfunction "GND_G1") (pintype "power_in"))
      (node (ref "J2") (pin "G2") (pinfunction "GND_G2") (pintype "power_in"))
      (node (ref "J2") (pin "G3") (pinfunction "GND_G3") (pintype "power_in"))
      (node (ref "J3") (pin "14") (pinfunction "14_14") (pintype "bidirectional"))
      (node (ref "J3") (pin "2") (pinfunction "2_2") (pintype "bidirectional"))
      (node (ref "J3") (pin "6") (pinfunction "6_6") (pintype "bidirectional"))
      (node (ref "J4") (pin "14") (pinfunction "14_14") (pintype "bidirectional"))
      (node (ref "J4") (pin "17") (pinfunction "17_17") (pintype "bidirectional"))
      (node (ref "J4") (pin "20") (pinfunction "20_20") (pintype "bidirectional"))
      (node (ref "J4") (pin "23") (pinfunction "23_23") (pintype "bidirectional"))
      (node (ref "J4") (pin "26") (pinfunction "26_26") (pintype "bidirectional"))
      (node (ref "J4") (pin "9") (pinfunction "9_9") (pintype "bidirectional"))
      (node (ref "JP1") (pin "1") (pinfunction "1_1") (pintype "passive"))
      (node (ref "JP3") (pin "3") (pinfunction "3_3") (pintype "passive"))
      (node (ref "JP3") (pin "5") (pinfunction "5_5") (pintype "passive"))
      (node (ref "Q2") (pin "1") (pinfunction "S_1") (pintype "passive"))
      (node (ref "Q3") (pin "1") (pinfunction "S_1") (pintype "passive"))
      (node (ref "R13") (pin "2") (pinfunction "2_2") (pintype "passive"))
      (node (ref "R17") (pin "2") (pinfunction "2_2") (pintype "passive"))
      (node (ref "R22") (pin "2") (pinfunction "2_2") (pintype "passive"))
      (node (ref "R31") (pin "1") (pinfunction "1_1") (pintype "passive"))
      (node (ref "R32") (pin "1") (pinfunction "1_1") (pintype "passive"))
      (node (ref "R4") (pin "1") (pinfunction "1_1") (pintype "passive"))
      (node (ref "R5") (pin "2") (pinfunction "2_2") (pintype "passive"))
      (node (ref "R9") (pin "2") (pinfunction "2_2") (pintype "passive"))
      (node (ref "U1") (pin "1") (pinfunction "GND_1") (pintype "power_in"))
      (node (ref "U10") (pin "13") (pinfunction "MODE_13") (pintype "input"))
      (node (ref "U10") (pin "8") (pinfunction "VSS_8") (pintype "power_in"))
      (node (ref "U11") (pin "4") (pinfunction "GND_4") (pintype "power_in"))
      (node (ref "U11") (pin "5") (pinfunction "A2_5") (pintype "bidirectional"))
      (node (ref "U11") (pin "6") (pinfunction "A1_6") (pintype "bidirectional"))
      (node (ref "U11") (pin "7") (pinfunction "A0_7") (pintype "bidirectional"))
      (node (ref "U11") (pin "9") (pinfunction "EP_9") (pintype "power_in"))
      (node (ref "U12") (pin "25") (pinfunction "EPAD_25") (pintype "passive"))
      (node (ref "U12") (pin "9") (pinfunction "GND_9") (pintype "power_in"))
      (node (ref "U13") (pin "17") (pinfunction "SDO1_17") (pintype "bidirectional"))
      (node (ref "U13") (pin "20") (pinfunction "CSB3_20") (pintype "bidirectional"))
      (node (ref "U13") (pin "4") (pinfunction "GNDA_4") (pintype "power_in"))
      (node (ref "U13") (pin "6") (pinfunction "GNDIO_6") (pintype "power_in"))
      (node (ref "U15") (pin "1") (pinfunction "OE_1") (pintype "bidirectional"))
      (node (ref "U15") (pin "3") (pinfunction "GND_3") (pintype "bidirectional"))
      (node (ref "U16") (pin "P$4") (pinfunction "GND_P$4") (pintype "bidirectional"))
      (node (ref "U17") (pin "1") (pinfunction "GND_1") (pintype "power_in"))
      (node (ref "U2") (pin "2") (pinfunction "GND_2") (pintype "bidirectional"))
      (node (ref "U3") (pin "1") (pinfunction "GND_1") (pintype "bidirectional"))
      (node (ref "U3") (pin "10") (pinfunction "GND_10") (pintype "bidirectional"))
      (node (ref "U3") (pin "11") (pinfunction "GND_11") (pintype "bidirectional"))
      (node (ref "U3") (pin "20") (pinfunction "GND_20") (pintype "bidirectional"))
      (node (ref "U3") (pin "4") (pinfunction "OVP_4") (pintype "bidirectional"))
      (node (ref "U3") (pin "PAD") (pinfunction "GND_PAD") (pintype "bidirectional"))
      (node (ref "U4") (pin "5") (pinfunction "GND_5") (pintype "power_in"))
      (node (ref "U5") (pin "10") (pinfunction "VSS_10") (pintype "bidirectional"))
      (node (ref "U6") (pin "18") (pinfunction "GND1_18") (pintype "bidirectional"))
      (node (ref "U6") (pin "35") (pinfunction "GND2_35") (pintype "bidirectional"))
      (node (ref "U6") (pin "42") (pinfunction "GND3_42") (pintype "bidirectional"))
      (node (ref "U6") (pin "5") (pinfunction "GNDANA_5") (pintype "bidirectional"))
      (node (ref "U7") (pin "2") (pinfunction "GND_2") (pintype "bidirectional"))
      (node (ref "U8") (pin "2") (pinfunction "GND_2") (pintype "bidirectional"))
      (node (ref "U8") (pin "4") (pinfunction "GND_4") (pintype "bidirectional"))
      (node (ref "U8") (pin "5") (pinfunction "GND_5") (pintype "bidirectional"))
    )
    (net (code "25") (name "I0") (class "Default")
      (node (ref "U12") (pin "17") (pinfunction "P17_17") (pintype "bidirectional"))
    )
    (net (code "26") (name "I1") (class "Default")
      (node (ref "U12") (pin "16") (pinfunction "P16_16") (pintype "bidirectional"))
    )
    (net (code "27") (name "IMUDR") (class "Default")
      (node (ref "U10") (pin "9") (pinfunction "DIN_9") (pintype "input"))
      (node (ref "U13") (pin "2") (pinfunction "DRDYM_2") (pintype "bidirectional"))
    )
    (net (code "28") (name "IMUINT1") (class "Default")
      (node (ref "U10") (pin "5") (pinfunction "BIN_5") (pintype "input"))
      (node (ref "U13") (pin "19") (pinfunction "INT1_19") (pintype "bidirectional"))
    )
    (net (code "29") (name "IMUINT2") (class "Default")
      (node (ref "U10") (pin "7") (pinfunction "CIN_7") (pintype "input"))
      (node (ref "U13") (pin "1") (pinfunction "INT2_1") (pintype "bidirectional"))
    )
    (net (code "30") (name "IMUINT3") (class "Default")
      (node (ref "U10") (pin "3") (pinfunction "AIN_3") (pintype "input"))
      (node (ref "U13") (pin "14") (pinfunction "INT3_14") (pintype "bidirectional"))
    )
    (net (code "31") (name "IMUINT4") (class "Default")
      (node (ref "U10") (pin "11") (pinfunction "EIN_11") (pintype "input"))
      (node (ref "U13") (pin "15") (pinfunction "INT4_15") (pintype "bidirectional"))
    )
    (net (code "32") (name "IMUINT5") (class "Default")
      (node (ref "U10") (pin "14") (pinfunction "FIN_14") (pintype "input"))
      (node (ref "U13") (pin "10") (pinfunction "INT5_10") (pintype "bidirectional"))
    )
    (net (code "33") (name "IOEINT") (class "Default")
      (node (ref "U15") (pin "4") (pinfunction "Y_4") (pintype "bidirectional"))
      (node (ref "U6") (pin "26") (pinfunction "PA17/I2C/EIC/SCOM1PAD1+/TC2_26") (pintype "bidirectional"))
    )
    (net (code "34") (name "I_SENSE") (class "Default")
      (node (ref "C12") (pin "1") (pinfunction "1_1") (pintype "passive"))
      (node (ref "R5") (pin "1") (pinfunction "1_1") (pintype "passive"))
      (node (ref "U3") (pin "8") (pinfunction "IOUT_8") (pintype "bidirectional"))
      (node (ref "U6") (pin "10") (pinfunction "PA05/EIC/AIN5/SCOM0PAD1_10") (pintype "bidirectional"))
    )
    (net (code "35") (name "LED_CTRL") (class "Default")
      (node (ref "U2") (pin "4") (pinfunction "EN_4") (pintype "bidirectional"))
      (node (ref "U6") (pin "14") (pinfunction "PA09/I2C/EIC/AIN17/SCOM2PAD1+/TC0_14") (pintype "bidirectional"))
    )
    (net (code "36") (name "LED_GND") (class "Default")
      (node (ref "J4") (pin "2") (pinfunction "2_2") (pintype "bidirectional"))
      (node (ref "R4") (pin "2") (pinfunction "2_2") (pintype "passive"))
      (node (ref "U2") (pin "3") (pinfunction "FB_3") (pintype "bidirectional"))
    )
    (net (code "37") (name "LED_V") (class "Default")
      (node (ref "C15") (pin "1") (pinfunction "1_1") (pintype "passive"))
      (node (ref "J4") (pin "1") (pinfunction "1_1") (pintype "bidirectional"))
      (node (ref "U2") (pin "1") (pinfunction "V_OUT_1") (pintype "bidirectional"))
    )
    (net (code "38") (name "M0") (class "Default")
      (node (ref "U12") (pin "11") (pinfunction "P11_11") (pintype "bidirectional"))
    )
    (net (code "39") (name "M1") (class "Default")
      (node (ref "U12") (pin "10") (pinfunction "P10_10") (pintype "bidirectional"))
    )
    (net (code "40") (name "MA1") (class "Default")
      (node (ref "J4") (pin "5") (pinfunction "5_5") (pintype "bidirectional"))
    )
    (net (code "41") (name "MA2") (class "Default")
      (node (ref "J4") (pin "6") (pinfunction "6_6") (pintype "bidirectional"))
    )
    (net (code "42") (name "MB1") (class "Default")
      (node (ref "J4") (pin "7") (pinfunction "7_7") (pintype "bidirectional"))
    )
    (net (code "43") (name "MB2") (class "Default")
      (node (ref "J4") (pin "8") (pinfunction "8_8") (pintype "bidirectional"))
    )
    (net (code "44") (name "MISO") (class "Default")
      (node (ref "J2") (pin "7") (pinfunction "DATA_OUT_7") (pintype "bidirectional"))
      (node (ref "U5") (pin "8") (pinfunction "DQ1_8") (pintype "bidirectional"))
      (node (ref "U6") (pin "21") (pinfunction "PA12/I2C/EIC/SCOM2PAD0+/TC2_21") (pintype "bidirectional"))
    )
    (net (code "45") (name "MOSI") (class "Default")
      (node (ref "J2") (pin "3") (pinfunction "DATA_IN_3") (pintype "bidirectional"))
      (node (ref "U5") (pin "15") (pinfunction "DQ0_15") (pintype "bidirectional"))
      (node (ref "U6") (pin "19") (pinfunction "PB10/EIC/SCOM4PAD2/TC5_19") (pintype "bidirectional"))
    )
    (net (code "46") (name "NENBL") (class "Default")
      (node (ref "U12") (pin "8") (pinfunction "P07_8") (pintype "bidirectional"))
    )
    (net (code "47") (name "NFAULT") (class "Default")
      (node (ref "U12") (pin "7") (pinfunction "P06_7") (pintype "bidirectional"))
    )
    (net (code "48") (name "NSLEEP") (class "Default")
      (node (ref "U12") (pin "14") (pinfunction "P14_14") (pintype "bidirectional"))
    )
    (net (code "49") (name "Net-(C6-Pad1)") (class "Default")
      (node (ref "C6") (pin "1") (pinfunction "1_1") (pintype "passive"))
      (node (ref "L2") (pin "P$1") (pinfunction "P$1_P$1") (pintype "bidirectional"))
      (node (ref "U3") (pin "15") (pinfunction "SW1_15") (pintype "bidirectional"))
      (node (ref "U3") (pin "16") (pinfunction "SW1_16") (pintype "bidirectional"))
    )
    (net (code "50") (name "Net-(C13-Pad1)") (class "Default")
      (node (ref "C13") (pin "1") (pinfunction "1_1") (pintype "passive"))
      (node (ref "L2") (pin "P$2") (pinfunction "P$2_P$2") (pintype "bidirectional"))
      (node (ref "U3") (pin "12") (pinfunction "SW2_12") (pintype "bidirectional"))
      (node (ref "U3") (pin "13") (pinfunction "SW2_13") (pintype "bidirectional"))
    )
    (net (code "51") (name "Net-(C14-Pad1)") (class "Default")
      (node (ref "C14") (pin "1") (pinfunction "1_1") (pintype "passive"))
      (node (ref "R6") (pin "1") (pinfunction "1_1") (pintype "passive"))
    )
    (net (code "52") (name "Net-(C18-Pad2)") (class "Default")
      (node (ref "C18") (pin "2") (pinfunction "2_2") (pintype "passive"))
      (node (ref "R10") (pin "2") (pinfunction "2_2") (pintype "passive"))
    )
    (net (code "53") (name "Net-(FB1-P$2)") (class "Default")
      (node (ref "C21") (pin "1") (pinfunction "1_1") (pintype "passive"))
      (node (ref "C22") (pin "1") (pinfunction "1_1") (pintype "passive"))
      (node (ref "FB1") (pin "2") (pinfunction "P$2_2") (pintype "passive"))
      (node (ref "U6") (pin "6") (pinfunction "VDDANA_6") (pintype "bidirectional"))
    )
    (net (code "54") (name "Net-(JP1-Pad2)") (class "Default")
      (node (ref "JP1") (pin "2") (pinfunction "2_2") (pintype "passive"))
      (node (ref "R1") (pin "1") (pinfunction "1_1") (pintype "passive"))
    )
    (net (code "55") (name "Net-(L1-2)") (class "Default")
      (node (ref "L1") (pin "P$2") (pinfunction "2_P$2") (pintype "passive"))
      (node (ref "U2") (pin "6") (pinfunction "SW_6") (pintype "bidirectional"))
    )
    (net (code "56") (name "Net-(Q2A-D)") (class "Default")
      (node (ref "Q2") (pin "5") (pinfunction "G_5") (pintype "passive"))
      (node (ref "Q2") (pin "6") (pinfunction "D_6") (pintype "passive"))
      (node (ref "R15") (pin "2") (pinfunction "2_2") (pintype "passive"))
    )
    (net (code "57") (name "Net-(Q3A-D)") (class "Default")
      (node (ref "Q3") (pin "5") (pinfunction "G_5") (pintype "passive"))
      (node (ref "Q3") (pin "6") (pinfunction "D_6") (pintype "passive"))
      (node (ref "R24") (pin "2") (pinfunction "2_2") (pintype "passive"))
    )
    (net (code "58") (name "Net-(Q4-B1)") (class "Default")
      (node (ref "Q4") (pin "1") (pinfunction "C1_1") (pintype "bidirectional"))
      (node (ref "Q4") (pin "2") (pinfunction "B1_2") (pintype "bidirectional"))
      (node (ref "Q4") (pin "3") (pinfunction "B2_3") (pintype "bidirectional"))
      (node (ref "R31") (pin "2") (pinfunction "2_2") (pintype "passive"))
    )
    (net (code "59") (name "Net-(Q4-C2)") (class "Default")
      (node (ref "Q4") (pin "4") (pinfunction "C2_4") (pintype "bidirectional"))
      (node (ref "Q5") (pin "1") (pinfunction "G_1") (pintype "passive"))
      (node (ref "R32") (pin "2") (pinfunction "2_2") (pintype "passive"))
    )
    (net (code "60") (name "Net-(U3-BST1)") (class "Default")
      (node (ref "C6") (pin "2") (pinfunction "2_2") (pintype "passive"))
      (node (ref "U3") (pin "17") (pinfunction "BST1_17") (pintype "bidirectional"))
    )
    (net (code "61") (name "Net-(U3-BST2)") (class "Default")
      (node (ref "C13") (pin "2") (pinfunction "2_2") (pintype "passive"))
      (node (ref "U3") (pin "14") (pinfunction "BST2_14") (pintype "bidirectional"))
    )
    (net (code "62") (name "Net-(U3-COMP)") (class "Default")
      (node (ref "C11") (pin "1") (pinfunction "1_1") (pintype "passive"))
      (node (ref "R6") (pin "2") (pinfunction "2_2") (pintype "passive"))
      (node (ref "U3") (pin "2") (pinfunction "COMP_2") (pintype "bidirectional"))
    )
    (net (code "63") (name "Net-(U3-FB)") (class "Default")
      (node (ref "C11") (pin "2") (pinfunction "2_2") (pintype "passive"))
      (node (ref "C14") (pin "2") (pinfunction "2_2") (pintype "passive"))
      (node (ref "R10") (pin "1") (pinfunction "1_1") (pintype "passive"))
      (node (ref "R8") (pin "2") (pinfunction "2_2") (pintype "passive"))
      (node (ref "R9") (pin "1") (pinfunction "1_1") (pintype "passive"))
      (node (ref "U3") (pin "3") (pinfunction "FB_3") (pintype "bidirectional"))
    )
    (net (code "64") (name "Net-(U3-PWM{slash}SYNC)") (class "Default")
      (node (ref "R33") (pin "1") (pinfunction "1_1") (pintype "passive"))
      (node (ref "U3") (pin "19") (pinfunction "PWM/SYNC_19") (pintype "bidirectional"))
    )
    (net (code "65") (name "Net-(U3-VCC)") (class "Default")
      (node (ref "C4") (pin "1") (pinfunction "1_1") (pintype "passive"))
      (node (ref "D4") (pin "C") (pinfunction "C_C") (pintype "passive"))
      (node (ref "R33") (pin "2") (pinfunction "2_2") (pintype "passive"))
      (node (ref "U3") (pin "18") (pinfunction "VCC_18") (pintype "bidirectional"))
    )
    (net (code "66") (name "Net-(U4-VBAT)") (class "Default")
      (node (ref "B1") (pin "1") (pinfunction "+_1") (pintype "power_in"))
      (node (ref "B1") (pin "2") (pinfunction "+_2") (pintype "power_in"))
      (node (ref "C5") (pin "1") (pinfunction "1_1") (pintype "passive"))
      (node (ref "U4") (pin "6") (pinfunction "VBAT_6") (pintype "power_in"))
    )
    (net (code "67") (name "Net-(U5-DQ3{slash}~{HOLD})") (class "Default")
      (node (ref "R14") (pin "2") (pinfunction "2_2") (pintype "passive"))
      (node (ref "U5") (pin "1") (pinfunction "DQ3/~{HOLD}_1") (pintype "bidirectional"))
      (node (ref "U5") (pin "3") (pinfunction "~{RESET}_3") (pintype "bidirectional"))
    )
    (net (code "68") (name "Net-(U6-VCC)") (class "Default")
      (node (ref "C20") (pin "1") (pinfunction "1_1") (pintype "passive"))
      (node (ref "L3") (pin "2") (pinfunction "2_2") (pintype "passive"))
      (node (ref "U6") (pin "44") (pinfunction "VCC_44") (pintype "bidirectional"))
    )
    (net (code "69") (name "Net-(U6-VDDCORE)") (class "Default")
      (node (ref "C27") (pin "1") (pinfunction "1_1") (pintype "passive"))
      (node (ref "U6") (pin "43") (pinfunction "VDDCORE_43") (pintype "bidirectional"))
    )
    (net (code "70") (name "Net-(U6-VDDIO1)") (class "Default")
      (node (ref "C25") (pin "1") (pinfunction "1_1") (pintype "passive"))
      (node (ref "L5") (pin "2") (pinfunction "2_2") (pintype "passive"))
      (node (ref "U6") (pin "17") (pinfunction "VDDIO1_17") (pintype "bidirectional"))
    )
    (net (code "71") (name "Net-(U6-VDDIO2)") (class "Default")
      (node (ref "C23") (pin "1") (pinfunction "1_1") (pintype "passive"))
      (node (ref "C26") (pin "1") (pinfunction "1_1") (pintype "passive"))
      (node (ref "L4") (pin "2") (pinfunction "2_2") (pintype "passive"))
      (node (ref "U6") (pin "36") (pinfunction "VDDIO2_36") (pintype "bidirectional"))
    )
    (net (code "72") (name "Net-(U7-BYP)") (class "Default")
      (node (ref "C29") (pin "1") (pinfunction "1_1") (pintype "passive"))
      (node (ref "U7") (pin "4") (pinfunction "BYP_4") (pintype "bidirectional"))
    )
    (net (code "73") (name "Net-(U10-AOUT)") (class "Default")
      (node (ref "U10") (pin "2") (pinfunction "AOUT_2") (pintype "output"))
      (node (ref "U12") (pin "1") (pinfunction "P00_1") (pintype "bidirectional"))
    )
    (net (code "74") (name "Net-(U10-BOUT)") (class "Default")
      (node (ref "U10") (pin "4") (pinfunction "BOUT_4") (pintype "output"))
      (node (ref "U12") (pin "2") (pinfunction "P01_2") (pintype "bidirectional"))
    )
    (net (code "75") (name "Net-(U10-COUT)") (class "Default")
      (node (ref "U10") (pin "6") (pinfunction "COUT_6") (pintype "output"))
      (node (ref "U12") (pin "3") (pinfunction "P02_3") (pintype "bidirectional"))
    )
    (net (code "76") (name "Net-(U10-DOUT)") (class "Default")
      (node (ref "U10") (pin "10") (pinfunction "DOUT_10") (pintype "output"))
      (node (ref "U12") (pin "4") (pinfunction "P03_4") (pintype "bidirectional"))
    )
    (net (code "77") (name "Net-(U10-EOUT)") (class "Default")
      (node (ref "U10") (pin "12") (pinfunction "EOUT_12") (pintype "output"))
      (node (ref "U12") (pin "5") (pinfunction "P04_5") (pintype "bidirectional"))
    )
    (net (code "78") (name "Net-(U10-FOUT)") (class "Default")
      (node (ref "U10") (pin "15") (pinfunction "FOUT_15") (pintype "output"))
      (node (ref "U12") (pin "6") (pinfunction "P05_6") (pintype "bidirectional"))
    )
    (net (code "79") (name "Net-(U11-OS)") (class "Default")
      (node (ref "R23") (pin "1") (pinfunction "1_1") (pintype "passive"))
      (node (ref "U11") (pin "3") (pinfunction "OS_3") (pintype "bidirectional"))
    )
    (net (code "80") (name "Net-(U12-INT)") (class "Default")
      (node (ref "U12") (pin "22") (pinfunction "INT_22") (pintype "output"))
      (node (ref "U15") (pin "2") (pinfunction "A_2") (pintype "bidirectional"))
    )
    (net (code "81") (name "Net-(U12-SCL)") (class "Default")
      (node (ref "R25") (pin "1") (pinfunction "1_1") (pintype "passive"))
      (node (ref "U12") (pin "19") (pinfunction "SCL_19") (pintype "bidirectional"))
      (node (ref "U17") (pin "7") (pinfunction "SCL2_7") (pintype "bidirectional"))
    )
    (net (code "82") (name "Net-(U12-SDA)") (class "Default")
      (node (ref "R27") (pin "1") (pinfunction "1_1") (pintype "passive"))
      (node (ref "U12") (pin "20") (pinfunction "SDA_20") (pintype "bidirectional"))
      (node (ref "U17") (pin "8") (pinfunction "SDA2_8") (pintype "bidirectional"))
    )
    (net (code "83") (name "Net-(U17-EN)") (class "Default")
      (node (ref "C41") (pin "1") (pinfunction "1_1") (pintype "passive"))
      (node (ref "R26") (pin "1") (pinfunction "1_1") (pintype "passive"))
      (node (ref "U17") (pin "5") (pinfunction "EN_5") (pintype "input"))
      (node (ref "U17") (pin "6") (pinfunction "VREF2_6") (pintype "power_in"))
    )
    (net (code "84") (name "PA27") (class "Default")
      (node (ref "U4") (pin "3") (pinfunction "~{INT}/SQW_3") (pintype "bidirectional"))
      (node (ref "U6") (pin "39") (pinfunction "PA27/EIC_39") (pintype "bidirectional"))
    )
    (net (code "85") (name "PB02") (class "Default")
      (node (ref "U6") (pin "47") (pinfunction "PB02/EIC/AIN10/SCOM5PAD0_47") (pintype "bidirectional"))
      (node (ref "U8") (pin "8") (pinfunction "INT1_8") (pintype "bidirectional"))
    )
    (net (code "86") (name "PB03") (class "Default")
      (node (ref "U6") (pin "48") (pinfunction "PB03/EIC/AIN11/SCOM5PAD1_48") (pintype "bidirectional"))
      (node (ref "U8") (pin "9") (pinfunction "INT2_9") (pintype "bidirectional"))
    )
    (net (code "87") (name "PB22") (class "Default")
      (node (ref "J2") (pin "2") (pinfunction "CS_2") (pintype "bidirectional"))
      (node (ref "U6") (pin "37") (pinfunction "PB22/EIC/SCOM5PAD2_37") (pintype "bidirectional"))
    )
    (net (code "88") (name "PB23") (class "Default")
      (node (ref "U5") (pin "7") (pinfunction "~{S}_7") (pintype "bidirectional"))
      (node (ref "U6") (pin "38") (pinfunction "PB23/EIC/SCOM5PAD3_38") (pintype "bidirectional"))
    )
    (net (code "89") (name "PI_D_N") (class "Default")
      (node (ref "J3") (pin "7") (pinfunction "7_7") (pintype "bidirectional"))
    )
    (net (code "90") (name "PI_D_P") (class "Default")
      (node (ref "J3") (pin "8") (pinfunction "8_8") (pintype "bidirectional"))
    )
    (net (code "91") (name "PI_KILL") (class "Default")
      (node (ref "U6") (pin "25") (pinfunction "PA16/I2C/EIC/SCOM1PAD0+/TC2_25") (pintype "bidirectional"))
    )
    (net (code "92") (name "RESET") (class "Default")
      (node (ref "C10") (pin "1") (pinfunction "1_1") (pintype "passive"))
      (node (ref "JP3") (pin "10") (pinfunction "10_10") (pintype "passive"))
      (node (ref "R1") (pin "2") (pinfunction "2_2") (pintype "passive"))
      (node (ref "R3") (pin "1") (pinfunction "1_1") (pintype "passive"))
      (node (ref "U6") (pin "40") (pinfunction "RESET_40") (pintype "bidirectional"))
    )
    (net (code "93") (name "RX0") (class "Default")
      (node (ref "J1") (pin "6") (pinfunction "6_6") (pintype "bidirectional"))
      (node (ref "U6") (pin "16") (pinfunction "PA11/EIC/AIN19/SCOM2PAD3+/TC1_16") (pintype "bidirectional"))
    )
    (net (code "94") (name "RX1") (class "Default")
      (node (ref "U6") (pin "28") (pinfunction "PA19/EIC/SCOM1PAD3+/TC3_28") (pintype "bidirectional"))
    )
    (net (code "95") (name "RX2") (class "Default")
      (node (ref "J3") (pin "9") (pinfunction "9_9") (pintype "bidirectional"))
      (node (ref "U6") (pin "30") (pinfunction "PA21/EIC/SCOM5PAD3+_30") (pintype "bidirectional"))
    )
    (net (code "96") (name "SCK") (class "Default")
      (node (ref "J2") (pin "5") (pinfunction "SCLK_5") (pintype "bidirectional"))
      (node (ref "U5") (pin "16") (pinfunction "C_16") (pintype "bidirectional"))
      (node (ref "U6") (pin "20") (pinfunction "PB11/EIC/SCOM4PAD3/TC5_20") (pintype "bidirectional"))
    )
    (net (code "97") (name "SCL") (class "Default")
      (node (ref "R28") (pin "3") (pinfunction "1_3") (pintype "passive"))
      (node (ref "U1") (pin "4") (pinfunction "SCL_4") (pintype "bidirectional"))
      (node (ref "U11") (pin "2") (pinfunction "SCL_2") (pintype "bidirectional"))
      (node (ref "U13") (pin "9") (pinfunction "SCX_9") (pintype "bidirectional"))
      (node (ref "U16") (pin "P$2") (pinfunction "SCL0_P$2") (pintype "bidirectional"))
      (node (ref "U17") (pin "3") (pinfunction "SCL1_3") (pintype "bidirectional"))
      (node (ref "U4") (pin "8") (pinfunction "SCL_8") (pintype "bidirectional"))
      (node (ref "U6") (pin "32") (pinfunction "PA23/I2C/EIC/SCOM5PAD1+/TC4_32") (pintype "bidirectional"))
      (node (ref "U8") (pin "14") (pinfunction "SCL/SCLK_14") (pintype "bidirectional"))
    )
    (net (code "98") (name "SCL_BUFF") (class "Default")
      (node (ref "J4") (pin "12") (pinfunction "12_12") (pintype "bidirectional"))
      (node (ref "R28") (pin "2") (pinfunction "1_2") (pintype "passive"))
      (node (ref "U16") (pin "P$7") (pinfunction "SCL1_P$7") (pintype "bidirectional"))
    )
    (net (code "99") (name "SDA") (class "Default")
      (node (ref "R28") (pin "4") (pinfunction "1_4") (pintype "passive"))
      (node (ref "U1") (pin "3") (pinfunction "SDA_3") (pintype "bidirectional"))
      (node (ref "U11") (pin "1") (pinfunction "SDA_1") (pintype "bidirectional"))
      (node (ref "U13") (pin "11") (pinfunction "SDX_11") (pintype "bidirectional"))
      (node (ref "U16") (pin "P$3") (pinfunction "SDA0_P$3") (pintype "bidirectional"))
      (node (ref "U17") (pin "4") (pinfunction "SDA1_4") (pintype "bidirectional"))
      (node (ref "U4") (pin "7") (pinfunction "SDA_7") (pintype "bidirectional"))
      (node (ref "U6") (pin "31") (pinfunction "PA22/I2C/EIC/SCOM5PAD0+/TC4_31") (pintype "bidirectional"))
      (node (ref "U8") (pin "13") (pinfunction "SDA/SDI/SDIO_13") (pintype "bidirectional"))
    )
    (net (code "100") (name "SDA_BUFF") (class "Default")
      (node (ref "J4") (pin "13") (pinfunction "13_13") (pintype "bidirectional"))
      (node (ref "R28") (pin "1") (pinfunction "1_1") (pintype "passive"))
      (node (ref "U16") (pin "P$6") (pinfunction "SDA1_P$6") (pintype "bidirectional"))
    )
    (net (code "101") (name "STEPFREQ") (class "Default")
      (node (ref "U6") (pin "13") (pinfunction "PA08/I2C/AIN16/SCOM2PAD0+/TC0_13") (pintype "bidirectional"))
    )
    (net (code "102") (name "SWDCLK") (class "Default")
      (node (ref "JP3") (pin "4") (pinfunction "4_4") (pintype "passive"))
      (node (ref "R30") (pin "1") (pinfunction "1_1") (pintype "passive"))
      (node (ref "U6") (pin "45") (pinfunction "PA30/EIC/SCOM1PAD2/SWDCLK_45") (pintype "bidirectional"))
    )
    (net (code "103") (name "SWDIO") (class "Default")
      (node (ref "JP3") (pin "2") (pinfunction "2_2") (pintype "passive"))
      (node (ref "U6") (pin "46") (pinfunction "PA31/EIC/SCOM1PAD3/SWDIO_46") (pintype "bidirectional"))
    )
    (net (code "104") (name "SYNC") (class "Default")
      (node (ref "U6") (pin "24") (pinfunction "PA15/XOUT/EIC/SCOM2PAD3+/TC3_24") (pintype "bidirectional"))
    )
    (net (code "105") (name "TX0") (class "Default")
      (node (ref "J1") (pin "7") (pinfunction "7_7") (pintype "bidirectional"))
      (node (ref "U6") (pin "15") (pinfunction "PA10/EIC/AIN18/SCOM2PAD2+/TC1_15") (pintype "bidirectional"))
    )
    (net (code "106") (name "TX1") (class "Default")
      (node (ref "U6") (pin "27") (pinfunction "PA18/EIC/SCOM1PAD2+/TC3_27") (pintype "bidirectional"))
    )
    (net (code "107") (name "TX2") (class "Default")
      (node (ref "J3") (pin "10") (pinfunction "10_10") (pintype "bidirectional"))
      (node (ref "U6") (pin "29") (pinfunction "PA20/EIC/SCOM5PAD2+_29") (pintype "bidirectional"))
    )
    (net (code "108") (name "USB_D_N") (class "Default")
      (node (ref "J3") (pin "4") (pinfunction "4_4") (pintype "bidirectional"))
      (node (ref "U6") (pin "33") (pinfunction "PA24/EIC/SCOM3PAD2+/TC5_33") (pintype "bidirectional"))
    )
    (net (code "109") (name "USB_D_P") (class "Default")
      (node (ref "J3") (pin "3") (pinfunction "3_3") (pintype "bidirectional"))
      (node (ref "U6") (pin "34") (pinfunction "PA25/EIC/SCOM3PAD3+/TC5_34") (pintype "bidirectional"))
    )
    (net (code "110") (name "VCC") (class "Default")
      (node (ref "C2") (pin "1") (pinfunction "1_1") (pintype "passive"))
      (node (ref "C42") (pin "1") (pinfunction "1_1") (pintype "passive"))
      (node (ref "J1") (pin "1") (pinfunction "1_1") (pintype "bidirectional"))
      (node (ref "J1") (pin "2") (pinfunction "2_2") (pintype "bidirectional"))
      (node (ref "U3") (pin "5") (pinfunction "VIN_5") (pintype "bidirectional"))
      (node (ref "U3") (pin "6") (pinfunction "VIN_6") (pintype "bidirectional"))
      (node (ref "U3") (pin "7") (pinfunction "RUN_7") (pintype "bidirectional"))
    )
    (net (code "111") (name "VREFA") (class "Default")
      (node (ref "C35") (pin "1") (pinfunction "1_1") (pintype "passive"))
      (node (ref "L6") (pin "1") (pinfunction "1_1") (pintype "passive"))
      (node (ref "U6") (pin "4") (pinfunction "PA03/EIC/REF/AI/VREFA_4") (pintype "bidirectional"))
    )
    (net (code "112") (name "V_SENSE") (class "Default")
      (node (ref "R16") (pin "2") (pinfunction "2_2") (pintype "passive"))
      (node (ref "R17") (pin "1") (pinfunction "1_1") (pintype "passive"))
      (node (ref "U6") (pin "3") (pinfunction "PA02/EIC/AIN_3") (pintype "bidirectional"))
    )
    (net (code "113") (name "XIN32") (class "Default")
      (node (ref "C7") (pin "1") (pinfunction "1_1") (pintype "passive"))
      (node (ref "U6") (pin "1") (pinfunction "PA00/XIN32/EIC/SCOM1PAD0_1") (pintype "bidirectional"))
      (node (ref "XTAL1") (pin "P2") (pinfunction "2_P2") (pintype "bidirectional"))
    )
    (net (code "114") (name "XOUT32") (class "Default")
      (node (ref "C8") (pin "1") (pinfunction "1_1") (pintype "passive"))
      (node (ref "U6") (pin "2") (pinfunction "PA01/XOUT32/EIC/SCOM1PAD1_2") (pintype "bidirectional"))
      (node (ref "XTAL1") (pin "P1") (pinfunction "1_P1") (pintype "bidirectional"))
    )
    (net (code "115") (name "unconnected-(J1-Pad8)") (class "Default")
      (node (ref "J1") (pin "8") (pinfunction "8_8") (pintype "bidirectional"))
    )
    (net (code "116") (name "unconnected-(J1-Pad9)") (class "Default")
      (node (ref "J1") (pin "9") (pinfunction "9_9") (pintype "bidirectional"))
    )
    (net (code "117") (name "unconnected-(J2-CD-PadCD1)") (class "Default")
      (node (ref "J2") (pin "CD1") (pinfunction "CD_CD1") (pintype "bidirectional"))
    )
    (net (code "118") (name "unconnected-(J2-DAT1-Pad8)") (class "Default")
      (node (ref "J2") (pin "8") (pinfunction "DAT1_8") (pintype "bidirectional"))
    )
    (net (code "119") (name "unconnected-(J2-DAT2-Pad1)") (class "Default")
      (node (ref "J2") (pin "1") (pinfunction "DAT2_1") (pintype "bidirectional"))
    )
    (net (code "120") (name "unconnected-(J3-Pad11)") (class "Default")
      (node (ref "J3") (pin "11") (pinfunction "11_11") (pintype "bidirectional"))
    )
    (net (code "121") (name "unconnected-(J3-Pad12)") (class "Default")
      (node (ref "J3") (pin "12") (pinfunction "12_12") (pintype "bidirectional"))
    )
    (net (code "122") (name "unconnected-(J3-Pad13)") (class "Default")
      (node (ref "J3") (pin "13") (pinfunction "13_13") (pintype "bidirectional"))
    )
    (net (code "123") (name "unconnected-(J3-Pad15)") (class "Default")
      (node (ref "J3") (pin "15") (pinfunction "15_15") (pintype "bidirectional"))
    )
    (net (code "124") (name "unconnected-(J4-Pad10)") (class "Default")
      (node (ref "J4") (pin "10") (pinfunction "10_10") (pintype "bidirectional"))
    )
    (net (code "125") (name "unconnected-(J4-Pad11)") (class "Default")
      (node (ref "J4") (pin "11") (pinfunction "11_11") (pintype "bidirectional"))
    )
    (net (code "126") (name "unconnected-(J4-Pad16)") (class "Default")
      (node (ref "J4") (pin "16") (pinfunction "16_16") (pintype "bidirectional"))
    )
    (net (code "127") (name "unconnected-(JP3-Pad6)") (class "Default")
      (node (ref "JP3") (pin "6") (pinfunction "6_6") (pintype "passive"))
    )
    (net (code "128") (name "unconnected-(JP3-Pad7)") (class "Default")
      (node (ref "JP3") (pin "7") (pinfunction "7_7") (pintype "passive"))
    )
    (net (code "129") (name "unconnected-(JP3-Pad8)") (class "Default")
      (node (ref "JP3") (pin "8") (pinfunction "8_8") (pintype "passive"))
    )
    (net (code "130") (name "unconnected-(JP3-Pad9)") (class "Default")
      (node (ref "JP3") (pin "9") (pinfunction "9_9") (pintype "passive"))
    )
    (net (code "131") (name "unconnected-(U1-NC-Pad5)") (class "Default")
      (node (ref "U1") (pin "5") (pinfunction "NC_5") (pintype "no_connect"))
    )
    (net (code "132") (name "unconnected-(U1-NC-Pad6)") (class "Default")
      (node (ref "U1") (pin "6") (pinfunction "NC_6") (pintype "no_connect"))
    )
    (net (code "133") (name "unconnected-(U1-NC-Pad7)") (class "Default")
      (node (ref "U1") (pin "7") (pinfunction "NC_7") (pintype "no_connect"))
    )
    (net (code "134") (name "unconnected-(U1-NC-Pad8)") (class "Default")
      (node (ref "U1") (pin "8") (pinfunction "NC_8") (pintype "no_connect"))
    )
    (net (code "135") (name "unconnected-(U4-32KHZ-Pad1)") (class "Default")
      (node (ref "U4") (pin "1") (pinfunction "32KHZ_1") (pintype "bidirectional"))
    )
    (net (code "136") (name "unconnected-(U4-~{RST}-Pad4)") (class "Default")
      (node (ref "U4") (pin "4") (pinfunction "~{RST}_4") (pintype "bidirectional"))
    )
    (net (code "137") (name "unconnected-(U5-DNU-Pad4)") (class "Default")
      (node (ref "U5") (pin "4") (pinfunction "DNU_4") (pintype "bidirectional"))
    )
    (net (code "138") (name "unconnected-(U5-DNU-Pad5)") (class "Default")
      (node (ref "U5") (pin "5") (pinfunction "DNU_5") (pintype "bidirectional"))
    )
    (net (code "139") (name "unconnected-(U5-DNU-Pad6)") (class "Default")
      (node (ref "U5") (pin "6") (pinfunction "DNU_6") (pintype "bidirectional"))
    )
    (net (code "140") (name "unconnected-(U5-DNU-Pad11)") (class "Default")
      (node (ref "U5") (pin "11") (pinfunction "DNU_11") (pintype "bidirectional"))
    )
    (net (code "141") (name "unconnected-(U5-DNU-Pad12)") (class "Default")
      (node (ref "U5") (pin "12") (pinfunction "DNU_12") (pintype "bidirectional"))
    )
    (net (code "142") (name "unconnected-(U5-DNU-Pad13)") (class "Default")
      (node (ref "U5") (pin "13") (pinfunction "DNU_13") (pintype "bidirectional"))
    )
    (net (code "143") (name "unconnected-(U5-DNU-Pad14)") (class "Default")
      (node (ref "U5") (pin "14") (pinfunction "DNU_14") (pintype "bidirectional"))
    )
    (net (code "144") (name "unconnected-(U5-DQ2{slash}~{W}-Pad9)") (class "Default")
      (node (ref "U5") (pin "9") (pinfunction "DQ2/~{W}_9") (pintype "bidirectional"))
    )
    (net (code "145") (name "unconnected-(U6-PA04{slash}EIC{slash}REF{slash}AIN4{slash}SCOM0PAD0{slash}VREFB-Pad9)") (class "Default")
      (node (ref "U6") (pin "9") (pinfunction "PA04/EIC/REF/AIN4/SCOM0PAD0/VREFB_9") (pintype "bidirectional"))
    )
    (net (code "146") (name "unconnected-(U6-PA06{slash}EIC{slash}AIN6{slash}SCOM0PAD2-Pad11)") (class "Default")
      (node (ref "U6") (pin "11") (pinfunction "PA06/EIC/AIN6/SCOM0PAD2_11") (pintype "bidirectional"))
    )
    (net (code "147") (name "unconnected-(U6-PA07{slash}EIC{slash}AIN7{slash}SCOM0PAD3-Pad12)") (class "Default")
      (node (ref "U6") (pin "12") (pinfunction "PA07/EIC/AIN7/SCOM0PAD3_12") (pintype "bidirectional"))
    )
    (net (code "148") (name "unconnected-(U6-PA14{slash}XIN{slash}EIC{slash}SCOM2PAD2+{slash}TC3-Pad23)") (class "Default")
      (node (ref "U6") (pin "23") (pinfunction "PA14/XIN/EIC/SCOM2PAD2+/TC3_23") (pintype "bidirectional"))
    )
    (net (code "149") (name "unconnected-(U6-PB08{slash}EIC{slash}AIN2{slash}SCOM4PAD0{slash}TC4-Pad7)") (class "Default")
      (node (ref "U6") (pin "7") (pinfunction "PB08/EIC/AIN2/SCOM4PAD0/TC4_7") (pintype "bidirectional"))
    )
    (net (code "150") (name "unconnected-(U6-PB09{slash}EIC{slash}AIN3{slash}SCOM4PAD1{slash}{slash}TC4-Pad8)") (class "Default")
      (node (ref "U6") (pin "8") (pinfunction "PB09/EIC/AIN3/SCOM4PAD1//TC4_8") (pintype "bidirectional"))
    )
    (net (code "151") (name "unconnected-(U8-NC-Pad10)") (class "Default")
      (node (ref "U8") (pin "10") (pinfunction "NC_10") (pintype "no_connect"))
    )
    (net (code "152") (name "unconnected-(U8-RES-Pad3)") (class "Default")
      (node (ref "U8") (pin "3") (pinfunction "RES_3") (pintype "bidirectional"))
    )
    (net (code "153") (name "unconnected-(U8-RES-Pad11)") (class "Default")
      (node (ref "U8") (pin "11") (pinfunction "RES_11") (pintype "bidirectional"))
    )
    (net (code "154") (name "unconnected-(U13-CSB1-Pad16)") (class "Default")
      (node (ref "U13") (pin "16") (pinfunction "CSB1_16") (pintype "bidirectional"))
    )
    (net (code "155") (name "unconnected-(U13-CSB2-Pad5)") (class "Default")
      (node (ref "U13") (pin "5") (pinfunction "CSB2_5") (pintype "bidirectional"))
    )
    (net (code "156") (name "unconnected-(U13-NC-Pad8)") (class "Default")
      (node (ref "U13") (pin "8") (pinfunction "NC_8") (pintype "no_connect"))
    )
    (net (code "157") (name "unconnected-(U13-NC-Pad18)") (class "Default")
      (node (ref "U13") (pin "18") (pinfunction "NC_18") (pintype "no_connect"))
    )
  )
)
